# Sheet1.net
KiCad netlist of a schematic drawn in Altium Designer
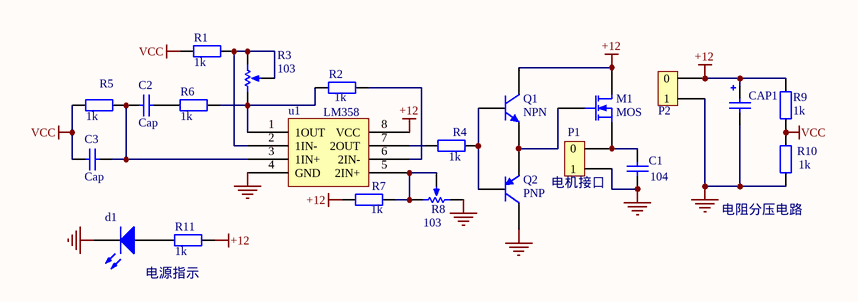
[diagram p0: Sheet1.SchDoc]

(export (version "E")
  (design (tool "Eeschema 10.0.6"))
  (components
    (comp (ref "C1") (value "104") (footprint "C") (libsource (lib "标准封装") (part "Cap")))
    (comp (ref "C2") (value "Cap") (footprint "Cap") (libsource (lib "标准封装") (part "Cap")))
    (comp (ref "C3") (value "Cap") (footprint "Cap") (libsource (lib "标准封装") (part "Cap")))
    (comp (ref "CAP1") (value "电解小电容") (footprint "电解小电容") (libsource (lib "标准封装") (part "电解小电容")))
    (comp (ref "d1") (value "LED") (footprint "LED") (libsource (lib "标准封装") (part "LED")))
    (comp (ref "M1") (value "MOS") (footprint "MOS1") (libsource (lib "标准封装") (part "MOS")))
    (comp (ref "P1") (value "双孔压线器") (footprint "双孔压线器") (libsource (lib "标准封装") (part "双孔压线器")))
    (comp (ref "P2") (value "双孔压线器") (footprint "双孔压线器") (libsource (lib "标准封装") (part "双孔压线器")))
    (comp (ref "Q1") (value "NPN") (footprint "npn - duplicate") (libsource (lib "标准封装") (part "NPN")))
    (comp (ref "Q2") (value "PNP") (footprint "pnp - duplicate") (libsource (lib "标准封装") (part "PNP")))
    (comp (ref "R1")
      (value "电阻")
      (footprint "电阻")
      (fields (field (name "ALTIUM_UNNAMED_1") "1k"))
      (libsource (lib "标准封装") (part "电阻"))
    )
    (comp (ref "R2")
      (value "电阻")
      (footprint "电阻")
      (fields (field (name "ALTIUM_UNNAMED_1") "1k"))
      (libsource (lib "标准封装") (part "电阻"))
    )
    (comp (ref "R3")
      (value "滑动变阻器")
      (footprint "滑动变阻器")
      (fields (field (name "ALTIUM_UNNAMED_1") "103"))
      (libsource (lib "标准封装") (part "滑动变阻器"))
    )
    (comp (ref "R4")
      (value "电阻")
      (footprint "电阻")
      (fields (field (name "ALTIUM_UNNAMED_1") "1k"))
      (libsource (lib "标准封装") (part "电阻"))
    )
    (comp (ref "R5")
      (value "电阻")
      (footprint "电阻")
      (fields (field (name "ALTIUM_UNNAMED_1") "1k"))
      (libsource (lib "") (part "电阻_1"))
    )
    (comp (ref "R6")
      (value "电阻")
      (footprint "电阻")
      (fields (field (name "ALTIUM_UNNAMED_1") "1k"))
      (libsource (lib "标准封装") (part "电阻"))
    )
    (comp (ref "R7")
      (value "电阻")
      (footprint "电阻")
      (fields (field (name "ALTIUM_UNNAMED_1") "1k"))
      (libsource (lib "标准封装") (part "电阻"))
    )
    (comp (ref "R8")
      (value "滑动变阻器")
      (footprint "滑动变阻器")
      (fields (field (name "ALTIUM_UNNAMED_1") "103"))
      (libsource (lib "标准封装") (part "滑动变阻器"))
    )
    (comp (ref "R9")
      (value "电阻")
      (footprint "电阻")
      (fields (field (name "ALTIUM_UNNAMED_1") "1k"))
      (libsource (lib "") (part "电阻_2"))
    )
    (comp (ref "R10")
      (value "电阻")
      (footprint "电阻")
      (fields (field (name "ALTIUM_UNNAMED_1") "1k"))
      (libsource (lib "") (part "电阻_2"))
    )
    (comp (ref "R11")
      (value "电阻")
      (footprint "电阻")
      (fields (field (name "ALTIUM_UNNAMED_1") "1k"))
      (libsource (lib "标准封装") (part "电阻"))
    )
    (comp (ref "u1") (value "LM358") (footprint "LM358") (libsource (lib "标准封装") (part "LM358")))
  )
  (nets
    (net (code "1") (name "+12") (class "Default")
      (node (ref "CAP1") (pin "2") (pinfunction "2_2") (pintype "passive"))
      (node (ref "M1") (pin "1") (pinfunction "D_1") (pintype "passive"))
      (node (ref "P2") (pin "0") (pinfunction "0_0") (pintype "passive"))
      (node (ref "Q1") (pin "1") (pinfunction "C_1") (pintype "passive"))
      (node (ref "R11") (pin "2") (pinfunction "2_2") (pintype "passive"))
      (node (ref "R7") (pin "1") (pinfunction "1_1") (pintype "passive"))
      (node (ref "R9") (pin "2") (pinfunction "2_2") (pintype "passive"))
      (node (ref "u1") (pin "8") (pinfunction "VCC_8") (pintype "passive"))
    )
    (net (code "2") (name "GND") (class "Default")
      (node (ref "C1") (pin "1") (pinfunction "1_1") (pintype "passive"))
      (node (ref "CAP1") (pin "1") (pinfunction "1_1") (pintype "passive"))
      (node (ref "P1") (pin "1") (pinfunction "1_1") (pintype "passive"))
      (node (ref "P2") (pin "1") (pinfunction "1_1") (pintype "passive"))
      (node (ref "Q2") (pin "1") (pinfunction "C_1") (pintype "passive"))
      (node (ref "R10") (pin "1") (pinfunction "1_1") (pintype "passive"))
      (node (ref "R8") (pin "1") (pinfunction "TOP_1") (pintype "passive"))
      (node (ref "d1") (pin "2") (pinfunction "K_2") (pintype "passive"))
      (node (ref "u1") (pin "4") (pinfunction "GND_4") (pintype "passive"))
    )
    (net (code "3") (name "Net-(C2-Pad2)") (class "Default")
      (node (ref "C2") (pin "2") (pinfunction "2_2") (pintype "passive"))
      (node (ref "R6") (pin "1") (pinfunction "1_1") (pintype "passive"))
    )
    (net (code "4") (name "Net-(M1-G)") (class "Default")
      (node (ref "M1") (pin "2") (pinfunction "G_2") (pintype "passive"))
      (node (ref "Q1") (pin "3") (pinfunction "E_3") (pintype "passive"))
      (node (ref "Q2") (pin "3") (pinfunction "E_3") (pintype "passive"))
    )
    (net (code "5") (name "Net-(M1-S)") (class "Default")
      (node (ref "C1") (pin "2") (pinfunction "2_2") (pintype "passive"))
      (node (ref "M1") (pin "3") (pinfunction "S_3") (pintype "passive"))
      (node (ref "P1") (pin "0") (pinfunction "0_0") (pintype "passive"))
    )
    (net (code "6") (name "Net-(Q1-B)") (class "Default")
      (node (ref "Q1") (pin "2") (pinfunction "B_2") (pintype "passive"))
      (node (ref "Q2") (pin "2") (pinfunction "B_2") (pintype "passive"))
      (node (ref "R4") (pin "2") (pinfunction "2_2") (pintype "passive"))
    )
    (net (code "7") (name "Net-(R3-BOT)") (class "Default")
      (node (ref "R1") (pin "2") (pinfunction "2_2") (pintype "passive"))
      (node (ref "R3") (pin "2") (pinfunction "BOT_2") (pintype "passive"))
      (node (ref "R3") (pin "3") (pinfunction "TAP_3") (pintype "passive"))
      (node (ref "u1") (pin "2") (pinfunction "1IN-_2") (pintype "passive"))
    )
    (net (code "8") (name "Net-(R3-TOP)") (class "Default")
      (node (ref "R2") (pin "1") (pinfunction "1_1") (pintype "passive"))
      (node (ref "R3") (pin "1") (pinfunction "TOP_1") (pintype "passive"))
      (node (ref "R6") (pin "2") (pinfunction "2_2") (pintype "passive"))
      (node (ref "u1") (pin "1") (pinfunction "1OUT_1") (pintype "passive"))
    )
    (net (code "9") (name "Net-(R8-BOT)") (class "Default")
      (node (ref "R7") (pin "2") (pinfunction "2_2") (pintype "passive"))
      (node (ref "R8") (pin "2") (pinfunction "BOT_2") (pintype "passive"))
      (node (ref "R8") (pin "3") (pinfunction "TAP_3") (pintype "passive"))
      (node (ref "u1") (pin "5") (pinfunction "2IN+_5") (pintype "passive"))
    )
    (net (code "10") (name "Net-(d1-A)") (class "Default")
      (node (ref "R11") (pin "1") (pinfunction "1_1") (pintype "passive"))
      (node (ref "d1") (pin "1") (pinfunction "A_1") (pintype "passive"))
    )
    (net (code "11") (name "Net-(u1-1IN+)") (class "Default")
      (node (ref "C2") (pin "1") (pinfunction "1_1") (pintype "passive"))
      (node (ref "C3") (pin "1") (pinfunction "1_1") (pintype "passive"))
      (node (ref "R5") (pin "1") (pinfunction "1_1") (pintype "passive"))
      (node (ref "u1") (pin "3") (pinfunction "1IN+_3") (pintype "passive"))
    )
    (net (code "12") (name "Net-(u1-2IN-)") (class "Default")
      (node (ref "R2") (pin "2") (pinfunction "2_2") (pintype "passive"))
      (node (ref "u1") (pin "6") (pinfunction "2IN-_6") (pintype "passive"))
    )
    (net (code "13") (name "Net-(u1-2OUT)") (class "Default")
      (node (ref "R4") (pin "1") (pinfunction "1_1") (pintype "passive"))
      (node (ref "u1") (pin "7") (pinfunction "2OUT_7") (pintype "passive"))
    )
    (net (code "14") (name "VCC") (class "Default")
      (node (ref "C3") (pin "2") (pinfunction "2_2") (pintype "passive"))
      (node (ref "R1") (pin "1") (pinfunction "1_1") (pintype "passive"))
      (node (ref "R10") (pin "2") (pinfunction "2_2") (pintype "passive"))
      (node (ref "R5") (pin "2") (pinfunction "2_2") (pintype "passive"))
      (node (ref "R9") (pin "1") (pinfunction "1_1") (pintype "passive"))
    )
  )
)
